# untitled.net
KiCad netlist of a schematic drawn in EAGLE
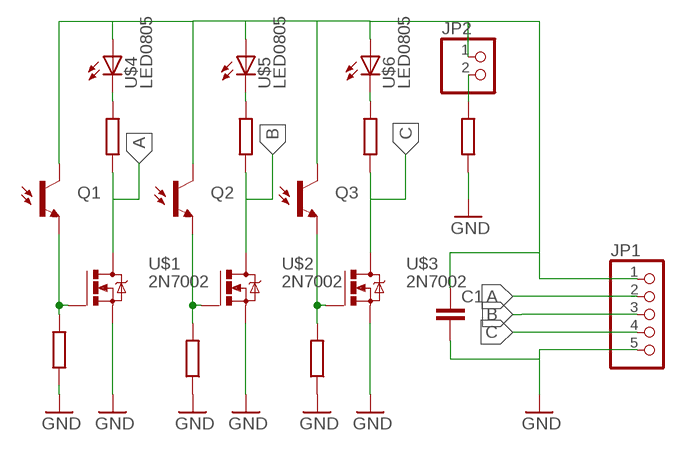
[diagram p0: schematic, sheet 1]

(export (version "E")
  (design (tool "Eeschema 10.0.6"))
  (components
    (comp (ref "C1")
      (value "CC0805")
      (footprint "eagle-import:C0805")
      (libsource (lib "eagle-import") (part "CC0805"))
    )
    (comp (ref "JP1")
      (value "PINHD-1X5")
      (footprint "eagle-import:1X05")
      (libsource (lib "eagle-import") (part "PINHD-1X5"))
    )
    (comp (ref "JP2")
      (value "PINHD-1X2")
      (footprint "eagle-import:1X02")
      (libsource (lib "eagle-import") (part "PINHD-1X2"))
    )
    (comp (ref "Q1")
      (value "PHOTOTRANSISTORPT17-21C-L41-TR8")
      (footprint "eagle-import:PT17-21C-L41-TR8")
      (libsource (lib "eagle-import") (part "PHOTOTRANSISTORPT17-21C-L41-TR8"))
    )
    (comp (ref "Q2")
      (value "PHOTOTRANSISTORPT17-21C-L41-TR8")
      (footprint "eagle-import:PT17-21C-L41-TR8")
      (libsource (lib "eagle-import") (part "PHOTOTRANSISTORPT17-21C-L41-TR8"))
    )
    (comp (ref "Q3")
      (value "PHOTOTRANSISTORPT17-21C-L41-TR8")
      (footprint "eagle-import:PT17-21C-L41-TR8")
      (libsource (lib "eagle-import") (part "PHOTOTRANSISTORPT17-21C-L41-TR8"))
    )
    (comp (ref "R1")
      (value "R0805")
      (footprint "eagle-import:R0805")
      (libsource (lib "eagle-import") (part "R0805"))
    )
    (comp (ref "R4")
      (value "R0805")
      (footprint "eagle-import:R0805")
      (libsource (lib "eagle-import") (part "R0805"))
    )
    (comp (ref "R5")
      (value "R0805")
      (footprint "eagle-import:R0805")
      (libsource (lib "eagle-import") (part "R0805"))
    )
    (comp (ref "R6")
      (value "R0805")
      (footprint "eagle-import:R0805")
      (libsource (lib "eagle-import") (part "R0805"))
    )
    (comp (ref "R7")
      (value "R0805")
      (footprint "eagle-import:R0805")
      (libsource (lib "eagle-import") (part "R0805"))
    )
    (comp (ref "R8")
      (value "R0805")
      (footprint "eagle-import:R0805")
      (libsource (lib "eagle-import") (part "R0805"))
    )
    (comp (ref "R9")
      (value "R0805")
      (footprint "eagle-import:R0805")
      (libsource (lib "eagle-import") (part "R0805"))
    )
    (comp (ref "U$1")
      (value "2N7002")
      (footprint "eagle-import:SOT23")
      (libsource (lib "eagle-import") (part "2N7002"))
    )
    (comp (ref "U$2")
      (value "2N7002")
      (footprint "eagle-import:SOT23")
      (libsource (lib "eagle-import") (part "2N7002"))
    )
    (comp (ref "U$3")
      (value "2N7002")
      (footprint "eagle-import:SOT23")
      (libsource (lib "eagle-import") (part "2N7002"))
    )
    (comp (ref "U$4")
      (value "LED0805")
      (footprint "eagle-import:0805-LED")
      (libsource (lib "eagle-import") (part "LED0805"))
    )
    (comp (ref "U$5")
      (value "LED0805")
      (footprint "eagle-import:0805-LED")
      (libsource (lib "eagle-import") (part "LED0805"))
    )
    (comp (ref "U$6")
      (value "LED0805")
      (footprint "eagle-import:0805-LED")
      (libsource (lib "eagle-import") (part "LED0805"))
    )
  )
  (nets
    (net (code "1") (name "A") (class "Default")
      (node (ref "JP1") (pin "2") (pinfunction "2_2") (pintype "passive"))
      (node (ref "R7") (pin "1") (pinfunction "1_1") (pintype "passive"))
      (node (ref "U$1") (pin "3") (pinfunction "D_3") (pintype "passive"))
    )
    (net (code "2") (name "B") (class "Default")
      (node (ref "JP1") (pin "3") (pinfunction "3_3") (pintype "passive"))
      (node (ref "R8") (pin "1") (pinfunction "1_1") (pintype "passive"))
      (node (ref "U$2") (pin "3") (pinfunction "D_3") (pintype "passive"))
    )
    (net (code "3") (name "C") (class "Default")
      (node (ref "JP1") (pin "4") (pinfunction "4_4") (pintype "passive"))
      (node (ref "R9") (pin "1") (pinfunction "1_1") (pintype "passive"))
      (node (ref "U$3") (pin "3") (pinfunction "D_3") (pintype "passive"))
    )
    (net (code "4") (name "GND") (class "Default")
      (node (ref "C1") (pin "2") (pinfunction "2_2") (pintype "passive"))
      (node (ref "JP1") (pin "5") (pinfunction "5_5") (pintype "passive"))
      (node (ref "R1") (pin "1") (pinfunction "1_1") (pintype "passive"))
      (node (ref "R4") (pin "1") (pinfunction "1_1") (pintype "passive"))
      (node (ref "R5") (pin "1") (pinfunction "1_1") (pintype "passive"))
      (node (ref "R6") (pin "1") (pinfunction "1_1") (pintype "passive"))
      (node (ref "U$1") (pin "2") (pinfunction "S_2") (pintype "passive"))
      (node (ref "U$2") (pin "2") (pinfunction "S_2") (pintype "passive"))
      (node (ref "U$3") (pin "2") (pinfunction "S_2") (pintype "passive"))
    )
    (net (code "5") (name "Net-(C1-Pad1)") (class "Default")
      (node (ref "C1") (pin "1") (pinfunction "1_1") (pintype "passive"))
      (node (ref "JP1") (pin "1") (pinfunction "1_1") (pintype "passive"))
      (node (ref "JP2") (pin "1") (pinfunction "1_1") (pintype "passive"))
      (node (ref "Q1") (pin "C") (pinfunction "C_C") (pintype "passive"))
      (node (ref "Q2") (pin "C") (pinfunction "C_C") (pintype "passive"))
      (node (ref "Q3") (pin "C") (pinfunction "C_C") (pintype "passive"))
      (node (ref "U$4") (pin "A") (pinfunction "A_A") (pintype "passive"))
      (node (ref "U$5") (pin "A") (pinfunction "A_A") (pintype "passive"))
      (node (ref "U$6") (pin "A") (pinfunction "A_A") (pintype "passive"))
    )
    (net (code "6") (name "Net-(JP2-Pad2)") (class "Default")
      (node (ref "JP2") (pin "2") (pinfunction "2_2") (pintype "passive"))
      (node (ref "R1") (pin "2") (pinfunction "2_2") (pintype "passive"))
    )
    (net (code "7") (name "Net-(R7-Pad2)") (class "Default")
      (node (ref "R7") (pin "2") (pinfunction "2_2") (pintype "passive"))
      (node (ref "U$4") (pin "C") (pinfunction "C_C") (pintype "passive"))
    )
    (net (code "8") (name "Net-(R8-Pad2)") (class "Default")
      (node (ref "R8") (pin "2") (pinfunction "2_2") (pintype "passive"))
      (node (ref "U$5") (pin "C") (pinfunction "C_C") (pintype "passive"))
    )
    (net (code "9") (name "Net-(R9-Pad2)") (class "Default")
      (node (ref "R9") (pin "2") (pinfunction "2_2") (pintype "passive"))
      (node (ref "U$6") (pin "C") (pinfunction "C_C") (pintype "passive"))
    )
    (net (code "10") (name "Net-(U$1-G)") (class "Default")
      (node (ref "Q1") (pin "E") (pinfunction "E_E") (pintype "passive"))
      (node (ref "R4") (pin "2") (pinfunction "2_2") (pintype "passive"))
      (node (ref "U$1") (pin "1") (pinfunction "G_1") (pintype "passive"))
    )
    (net (code "11") (name "Net-(U$2-G)") (class "Default")
      (node (ref "Q2") (pin "E") (pinfunction "E_E") (pintype "passive"))
      (node (ref "R5") (pin "2") (pinfunction "2_2") (pintype "passive"))
      (node (ref "U$2") (pin "1") (pinfunction "G_1") (pintype "passive"))
    )
    (net (code "12") (name "Net-(U$3-G)") (class "Default")
      (node (ref "Q3") (pin "E") (pinfunction "E_E") (pintype "passive"))
      (node (ref "R6") (pin "2") (pinfunction "2_2") (pintype "passive"))
      (node (ref "U$3") (pin "1") (pinfunction "G_1") (pintype "passive"))
    )
  )
)
